# ledcandle.net
KiCad netlist of a schematic drawn in EAGLE
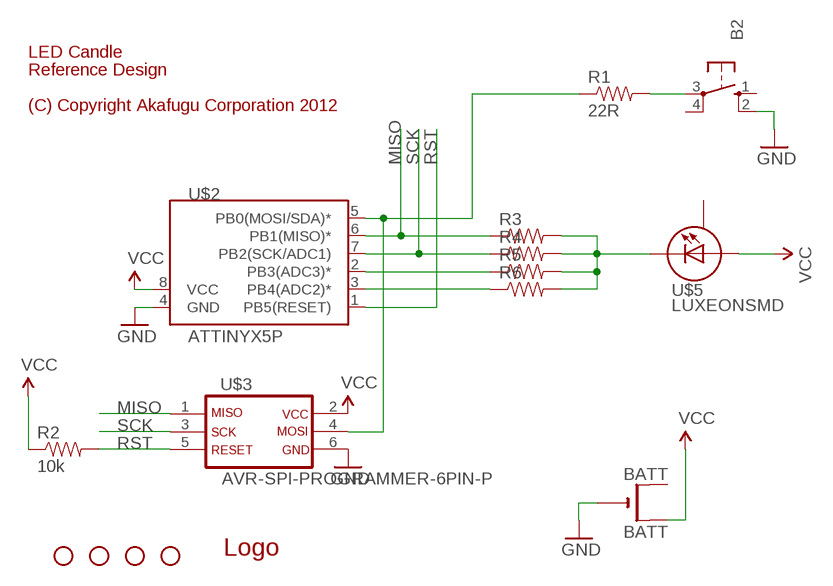
[diagram p0: schematic, sheet 1]

(export (version "E")
  (design (tool "Eeschema 10.0.6"))
  (components
    (comp (ref "B2")
      (value "10-XX")
      (footprint "eagle-import:B3F-10XX")
      (libsource (lib "eagle-import") (part "10-XX"))
    )
    (comp (ref "BATT")
      (value "BATT")
      (footprint "eagle-import:CR2032-THM-PAD")
      (libsource (lib "eagle-import") (part "COIN-CELL-CR2032-THM-PAD"))
    )
    (comp (ref "JP1")
      (value "STAND-OFF")
      (footprint "eagle-import:STAND-OFF")
      (libsource (lib "eagle-import") (part "STAND-OFF"))
    )
    (comp (ref "JP2")
      (value "STAND-OFF")
      (footprint "eagle-import:STAND-OFF")
      (libsource (lib "eagle-import") (part "STAND-OFF"))
    )
    (comp (ref "JP3")
      (value "STAND-OFF")
      (footprint "eagle-import:STAND-OFF")
      (libsource (lib "eagle-import") (part "STAND-OFF"))
    )
    (comp (ref "JP4")
      (value "STAND-OFF")
      (footprint "eagle-import:STAND-OFF")
      (libsource (lib "eagle-import") (part "STAND-OFF"))
    )
    (comp (ref "R1")
      (value "22R")
      (footprint "eagle-import:1_6W-RES-OUTLINE")
      (libsource (lib "eagle-import") (part "RESISTOR-PTH-1/6W-OUTLINE"))
    )
    (comp (ref "R2")
      (value "10k")
      (footprint "eagle-import:1_6W-RES-OUTLINE")
      (libsource (lib "eagle-import") (part "RESISTOR-PTH-1/6W-OUTLINE"))
    )
    (comp (ref "R3")
      (value "RESISTOR-PTH-1/6W-OUTLINE")
      (footprint "eagle-import:1_6W-RES-OUTLINE")
      (libsource (lib "eagle-import") (part "RESISTOR-PTH-1/6W-OUTLINE"))
    )
    (comp (ref "R4")
      (value "RESISTOR-PTH-1/6W-OUTLINE")
      (footprint "eagle-import:1_6W-RES-OUTLINE")
      (libsource (lib "eagle-import") (part "RESISTOR-PTH-1/6W-OUTLINE"))
    )
    (comp (ref "R5")
      (value "RESISTOR-PTH-1/6W-OUTLINE")
      (footprint "eagle-import:1_6W-RES-OUTLINE")
      (libsource (lib "eagle-import") (part "RESISTOR-PTH-1/6W-OUTLINE"))
    )
    (comp (ref "R6")
      (value "RESISTOR-PTH-1/6W-OUTLINE")
      (footprint "eagle-import:1_6W-RES-OUTLINE")
      (libsource (lib "eagle-import") (part "RESISTOR-PTH-1/6W-OUTLINE"))
    )
    (comp (ref "U$1")
      (value "OSHW-LOGO-FILL")
      (footprint "eagle-import:OSHW-LOGO-FILL")
      (libsource (lib "eagle-import") (part "OSHW-LOGO-FILL"))
    )
    (comp (ref "U$2")
      (value "ATTINYX5P")
      (footprint "eagle-import:DIL-8")
      (libsource (lib "eagle-import") (part "ATTINYX5P"))
    )
    (comp (ref "U$3")
      (value "AVR-SPI-PROGRAMMER-6PIN-P")
      (footprint "eagle-import:2X03")
      (libsource (lib "eagle-import") (part "AVR-SPI-PROGRAMMER-6PIN-P"))
    )
    (comp (ref "U$5")
      (value "LUXEONSMD")
      (footprint "eagle-import:LUXEON")
      (libsource (lib "eagle-import") (part "LUXEONSMD"))
    )
  )
  (nets
    (net (code "1") (name "/MISO") (class "Default")
      (node (ref "R3") (pin "1") (pinfunction "1_1") (pintype "passive"))
      (node (ref "U$2") (pin "6") (pinfunction "PB1(MISO)*_6") (pintype "bidirectional"))
      (node (ref "U$3") (pin "1") (pinfunction "1_1") (pintype "passive"))
    )
    (net (code "2") (name "/RST") (class "Default")
      (node (ref "R2") (pin "2") (pinfunction "2_2") (pintype "passive"))
      (node (ref "U$2") (pin "1") (pinfunction "PB5(RESET)_1") (pintype "bidirectional"))
      (node (ref "U$3") (pin "5") (pinfunction "5_5") (pintype "passive"))
    )
    (net (code "3") (name "/SCK") (class "Default")
      (node (ref "R4") (pin "1") (pinfunction "1_1") (pintype "passive"))
      (node (ref "U$2") (pin "7") (pinfunction "PB2(SCK/ADC1)_7") (pintype "bidirectional"))
      (node (ref "U$3") (pin "3") (pinfunction "3_3") (pintype "passive"))
    )
    (net (code "4") (name "GND") (class "Default")
      (node (ref "B2") (pin "2") (pinfunction "S1_2") (pintype "passive"))
      (node (ref "BATT") (pin "-") (pinfunction "-_-") (pintype "passive"))
      (node (ref "U$2") (pin "4") (pinfunction "GND_4") (pintype "bidirectional"))
      (node (ref "U$3") (pin "6") (pinfunction "6_6") (pintype "passive"))
    )
    (net (code "5") (name "Net-(B2-P)") (class "Default")
      (node (ref "B2") (pin "3") (pinfunction "P_3") (pintype "passive"))
      (node (ref "R1") (pin "2") (pinfunction "2_2") (pintype "passive"))
    )
    (net (code "6") (name "Net-(R3-Pad2)") (class "Default")
      (node (ref "R3") (pin "2") (pinfunction "2_2") (pintype "passive"))
      (node (ref "R4") (pin "2") (pinfunction "2_2") (pintype "passive"))
      (node (ref "R5") (pin "2") (pinfunction "2_2") (pintype "passive"))
      (node (ref "R6") (pin "2") (pinfunction "2_2") (pintype "passive"))
      (node (ref "U$5") (pin "C") (pinfunction "C_C") (pintype "passive"))
    )
    (net (code "7") (name "Net-(U$2-PB0(MOSI{slash}SDA)*)") (class "Default")
      (node (ref "R1") (pin "1") (pinfunction "1_1") (pintype "passive"))
      (node (ref "U$2") (pin "5") (pinfunction "PB0(MOSI/SDA)*_5") (pintype "bidirectional"))
      (node (ref "U$3") (pin "4") (pinfunction "4_4") (pintype "passive"))
    )
    (net (code "8") (name "Net-(U$2-PB3(ADC3)*)") (class "Default")
      (node (ref "R5") (pin "1") (pinfunction "1_1") (pintype "passive"))
      (node (ref "U$2") (pin "2") (pinfunction "PB3(ADC3)*_2") (pintype "bidirectional"))
    )
    (net (code "9") (name "Net-(U$2-PB4(ADC2)*)") (class "Default")
      (node (ref "R6") (pin "1") (pinfunction "1_1") (pintype "passive"))
      (node (ref "U$2") (pin "3") (pinfunction "PB4(ADC2)*_3") (pintype "bidirectional"))
    )
    (net (code "10") (name "VCC") (class "Default")
      (node (ref "BATT") (pin "+2") (pinfunction "+1_+2") (pintype "passive"))
      (node (ref "R2") (pin "1") (pinfunction "1_1") (pintype "passive"))
      (node (ref "U$2") (pin "8") (pinfunction "VCC_8") (pintype "bidirectional"))
      (node (ref "U$3") (pin "2") (pinfunction "2_2") (pintype "passive"))
      (node (ref "U$5") (pin "A") (pinfunction "A_A") (pintype "passive"))
    )
    (net (code "11") (name "unconnected-(B2-P1-Pad4)") (class "Default")
      (node (ref "B2") (pin "4") (pinfunction "P1_4") (pintype "passive"))
    )
    (net (code "12") (name "unconnected-(B2-S-Pad1)") (class "Default")
      (node (ref "B2") (pin "1") (pinfunction "S_1") (pintype "passive"))
    )
    (net (code "13") (name "unconnected-(BATT-+-Pad+1)") (class "Default")
      (node (ref "BATT") (pin "+1") (pinfunction "+_+1") (pintype "passive"))
    )
    (net (code "14") (name "unconnected-(U$5-PadS)") (class "Default")
      (node (ref "U$5") (pin "S") (pinfunction "S_S") (pintype "bidirectional"))
    )
  )
)
